# Schematic.net
KiCad netlist of a schematic drawn in Altium Designer
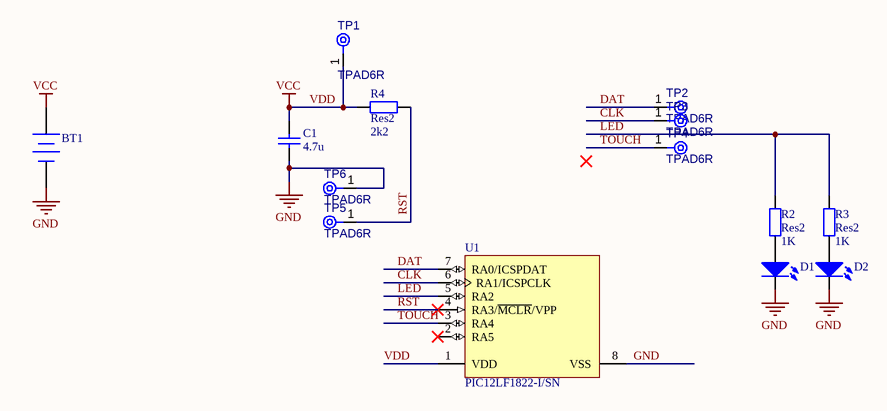
[diagram p0: Schematic.SchDoc]

(export (version "E")
  (design (tool "Eeschema 10.0.6"))
  (components
    (comp (ref "BT1")
      (value "Battery")
      (footprint "Moji Footprintovi:CR2032 SMD")
      (description "Multicell Battery")
      (fields (field (name "PUBLISHER") "Altium Limited"))
      (libsource (lib "Moji Schematici") (part "Battery"))
    )
    (comp (ref "C1")
      (value "4.7u")
      (footprint "Moji Footprintovi:0603 - CAP")
      (description "Capacitor")
      (fields (field (name "Comment") "Cap") (field (name "PUBLISHER") "Altium Limited"))
      (libsource (lib "Moji Schematici") (part "Cap"))
    )
    (comp (ref "D1")
      (value "LED")
      (footprint "Moji Footprintovi:0805 -  LED")
      (description "Typical RED GaAs LED")
      (fields (field (name "PUBLISHER") "Altium Limited"))
      (libsource (lib "Moji Schematici") (part "LED"))
    )
    (comp (ref "D2")
      (value "LED")
      (footprint "Moji Footprintovi:0805 -  LED")
      (description "Typical RED GaAs LED")
      (fields (field (name "PUBLISHER") "Altium Limited"))
      (libsource (lib "Moji Schematici") (part "LED"))
    )
    (comp (ref "R2")
      (value "Res2")
      (footprint "C1206")
      (description "Resistor")
      (fields (field (name "ALTIUM_VALUE") "1K") (field (name "PUBLISHER") "Altium Limited"))
      (libsource (lib "Miscellaneous Devices") (part "Res2"))
    )
    (comp (ref "R3")
      (value "Res2")
      (footprint "C1206")
      (description "Resistor")
      (fields (field (name "ALTIUM_VALUE") "1K") (field (name "PUBLISHER") "Altium Limited"))
      (libsource (lib "Miscellaneous Devices") (part "Res2"))
    )
    (comp (ref "R4")
      (value "Res2")
      (footprint "C1206")
      (description "Resistor")
      (fields (field (name "ALTIUM_VALUE") "2k2") (field (name "PUBLISHER") "Altium Limited"))
      (libsource (lib "") (part "Res2_1"))
    )
    (comp (ref "TP1")
      (value "TPAD6R")
      (footprint "TP06R")
      (description "0.6mm round")
      (libsource (lib "Test workspace") (part "CMP-001-0001-4"))
    )
    (comp (ref "TP2")
      (value "TPAD6R")
      (footprint "TP06R")
      (description "0.6mm round")
      (libsource (lib "Test workspace") (part "CMP-001-0001-4"))
    )
    (comp (ref "TP3")
      (value "TPAD6R")
      (footprint "TP06R")
      (description "0.6mm round")
      (libsource (lib "Test workspace") (part "CMP-001-0001-4"))
    )
    (comp (ref "TP4")
      (value "TPAD6R")
      (footprint "TP06R")
      (description "0.6mm round")
      (libsource (lib "Test workspace") (part "CMP-001-0001-4"))
    )
    (comp (ref "TP5")
      (value "TPAD6R")
      (footprint "TP06R")
      (description "0.6mm round")
      (libsource (lib "Test workspace") (part "CMP-001-0001-4"))
    )
    (comp (ref "TP6")
      (value "TPAD6R")
      (footprint "TP06R")
      (description "0.6mm round")
      (libsource (lib "Test workspace") (part "CMP-001-0001-4"))
    )
    (comp (ref "U1")
      (value "PIC12LF1822-I/SN")
      (footprint "MCHP-SOIC-SN8_N")
      (description "Flash Microcontroller with XLP Technology, 32 MHz, 5 I/O, -40 to 85 degC, 8-pin SOIC (SN8), Tube")
      (fields (field (name "MANUFACTURER") "Microchip"))
      (libsource (lib "Altium Content Vault") (part "MCHP-PIC12F1XXX_752_HV752-8"))
    )
  )
  (nets
    (net (code "1") (name "/CLK") (class "Default")
      (node (ref "TP3") (pin "1") (pinfunction "TP_1") (pintype "passive"))
      (node (ref "U1") (pin "6") (pinfunction "RA1/ICSPCLK_6") (pintype "bidirectional"))
    )
    (net (code "2") (name "/DAT") (class "Default")
      (node (ref "TP2") (pin "1") (pinfunction "TP_1") (pintype "passive"))
      (node (ref "U1") (pin "7") (pinfunction "RA0/ICSPDAT_7") (pintype "bidirectional"))
    )
    (net (code "3") (name "/LED") (class "Default")
      (node (ref "R2") (pin "2") (pinfunction "2_2") (pintype "passive"))
      (node (ref "R3") (pin "2") (pinfunction "2_2") (pintype "passive"))
      (node (ref "U1") (pin "5") (pinfunction "RA2_5") (pintype "bidirectional"))
    )
    (net (code "4") (name "/RST") (class "Default")
      (node (ref "R4") (pin "1") (pinfunction "1_1") (pintype "passive"))
      (node (ref "TP5") (pin "1") (pinfunction "TP_1") (pintype "passive"))
      (node (ref "U1") (pin "4") (pinfunction "RA3/~{MCLR}/VPP_4") (pintype "input"))
    )
    (net (code "5") (name "/TOUCH") (class "Default")
      (node (ref "TP4") (pin "1") (pinfunction "TP_1") (pintype "passive"))
      (node (ref "U1") (pin "3") (pinfunction "RA4_3") (pintype "bidirectional"))
    )
    (net (code "6") (name "GND") (class "Default")
      (node (ref "BT1") (pin "2") (pinfunction "-_2") (pintype "passive"))
      (node (ref "C1") (pin "1") (pinfunction "1_1") (pintype "passive"))
      (node (ref "D1") (pin "K") (pinfunction "K_K") (pintype "passive"))
      (node (ref "D2") (pin "K") (pinfunction "K_K") (pintype "passive"))
      (node (ref "TP6") (pin "1") (pinfunction "TP_1") (pintype "passive"))
      (node (ref "U1") (pin "8") (pinfunction "VSS_8") (pintype "power_in"))
    )
    (net (code "7") (name "Net-(D1-PadA)") (class "Default")
      (node (ref "D1") (pin "A") (pinfunction "A_A") (pintype "passive"))
      (node (ref "R2") (pin "1") (pinfunction "1_1") (pintype "passive"))
    )
    (net (code "8") (name "Net-(D2-PadA)") (class "Default")
      (node (ref "D2") (pin "A") (pinfunction "A_A") (pintype "passive"))
      (node (ref "R3") (pin "1") (pinfunction "1_1") (pintype "passive"))
    )
    (net (code "9") (name "VCC") (class "Default")
      (node (ref "BT1") (pin "1") (pinfunction "+_1") (pintype "passive"))
      (node (ref "C1") (pin "2") (pinfunction "2_2") (pintype "passive"))
      (node (ref "R4") (pin "2") (pinfunction "2_2") (pintype "passive"))
      (node (ref "TP1") (pin "1") (pinfunction "TP_1") (pintype "passive"))
      (node (ref "U1") (pin "1") (pinfunction "VDD_1") (pintype "power_in"))
    )
    (net (code "10") (name "unconnected-(U1-RA5-Pad2)") (class "Default")
      (node (ref "U1") (pin "2") (pinfunction "RA5_2") (pintype "bidirectional+no_connect"))
    )
  )
)
